# L1Demoscene_v4.net
KiCad netlist of a schematic drawn in EAGLE
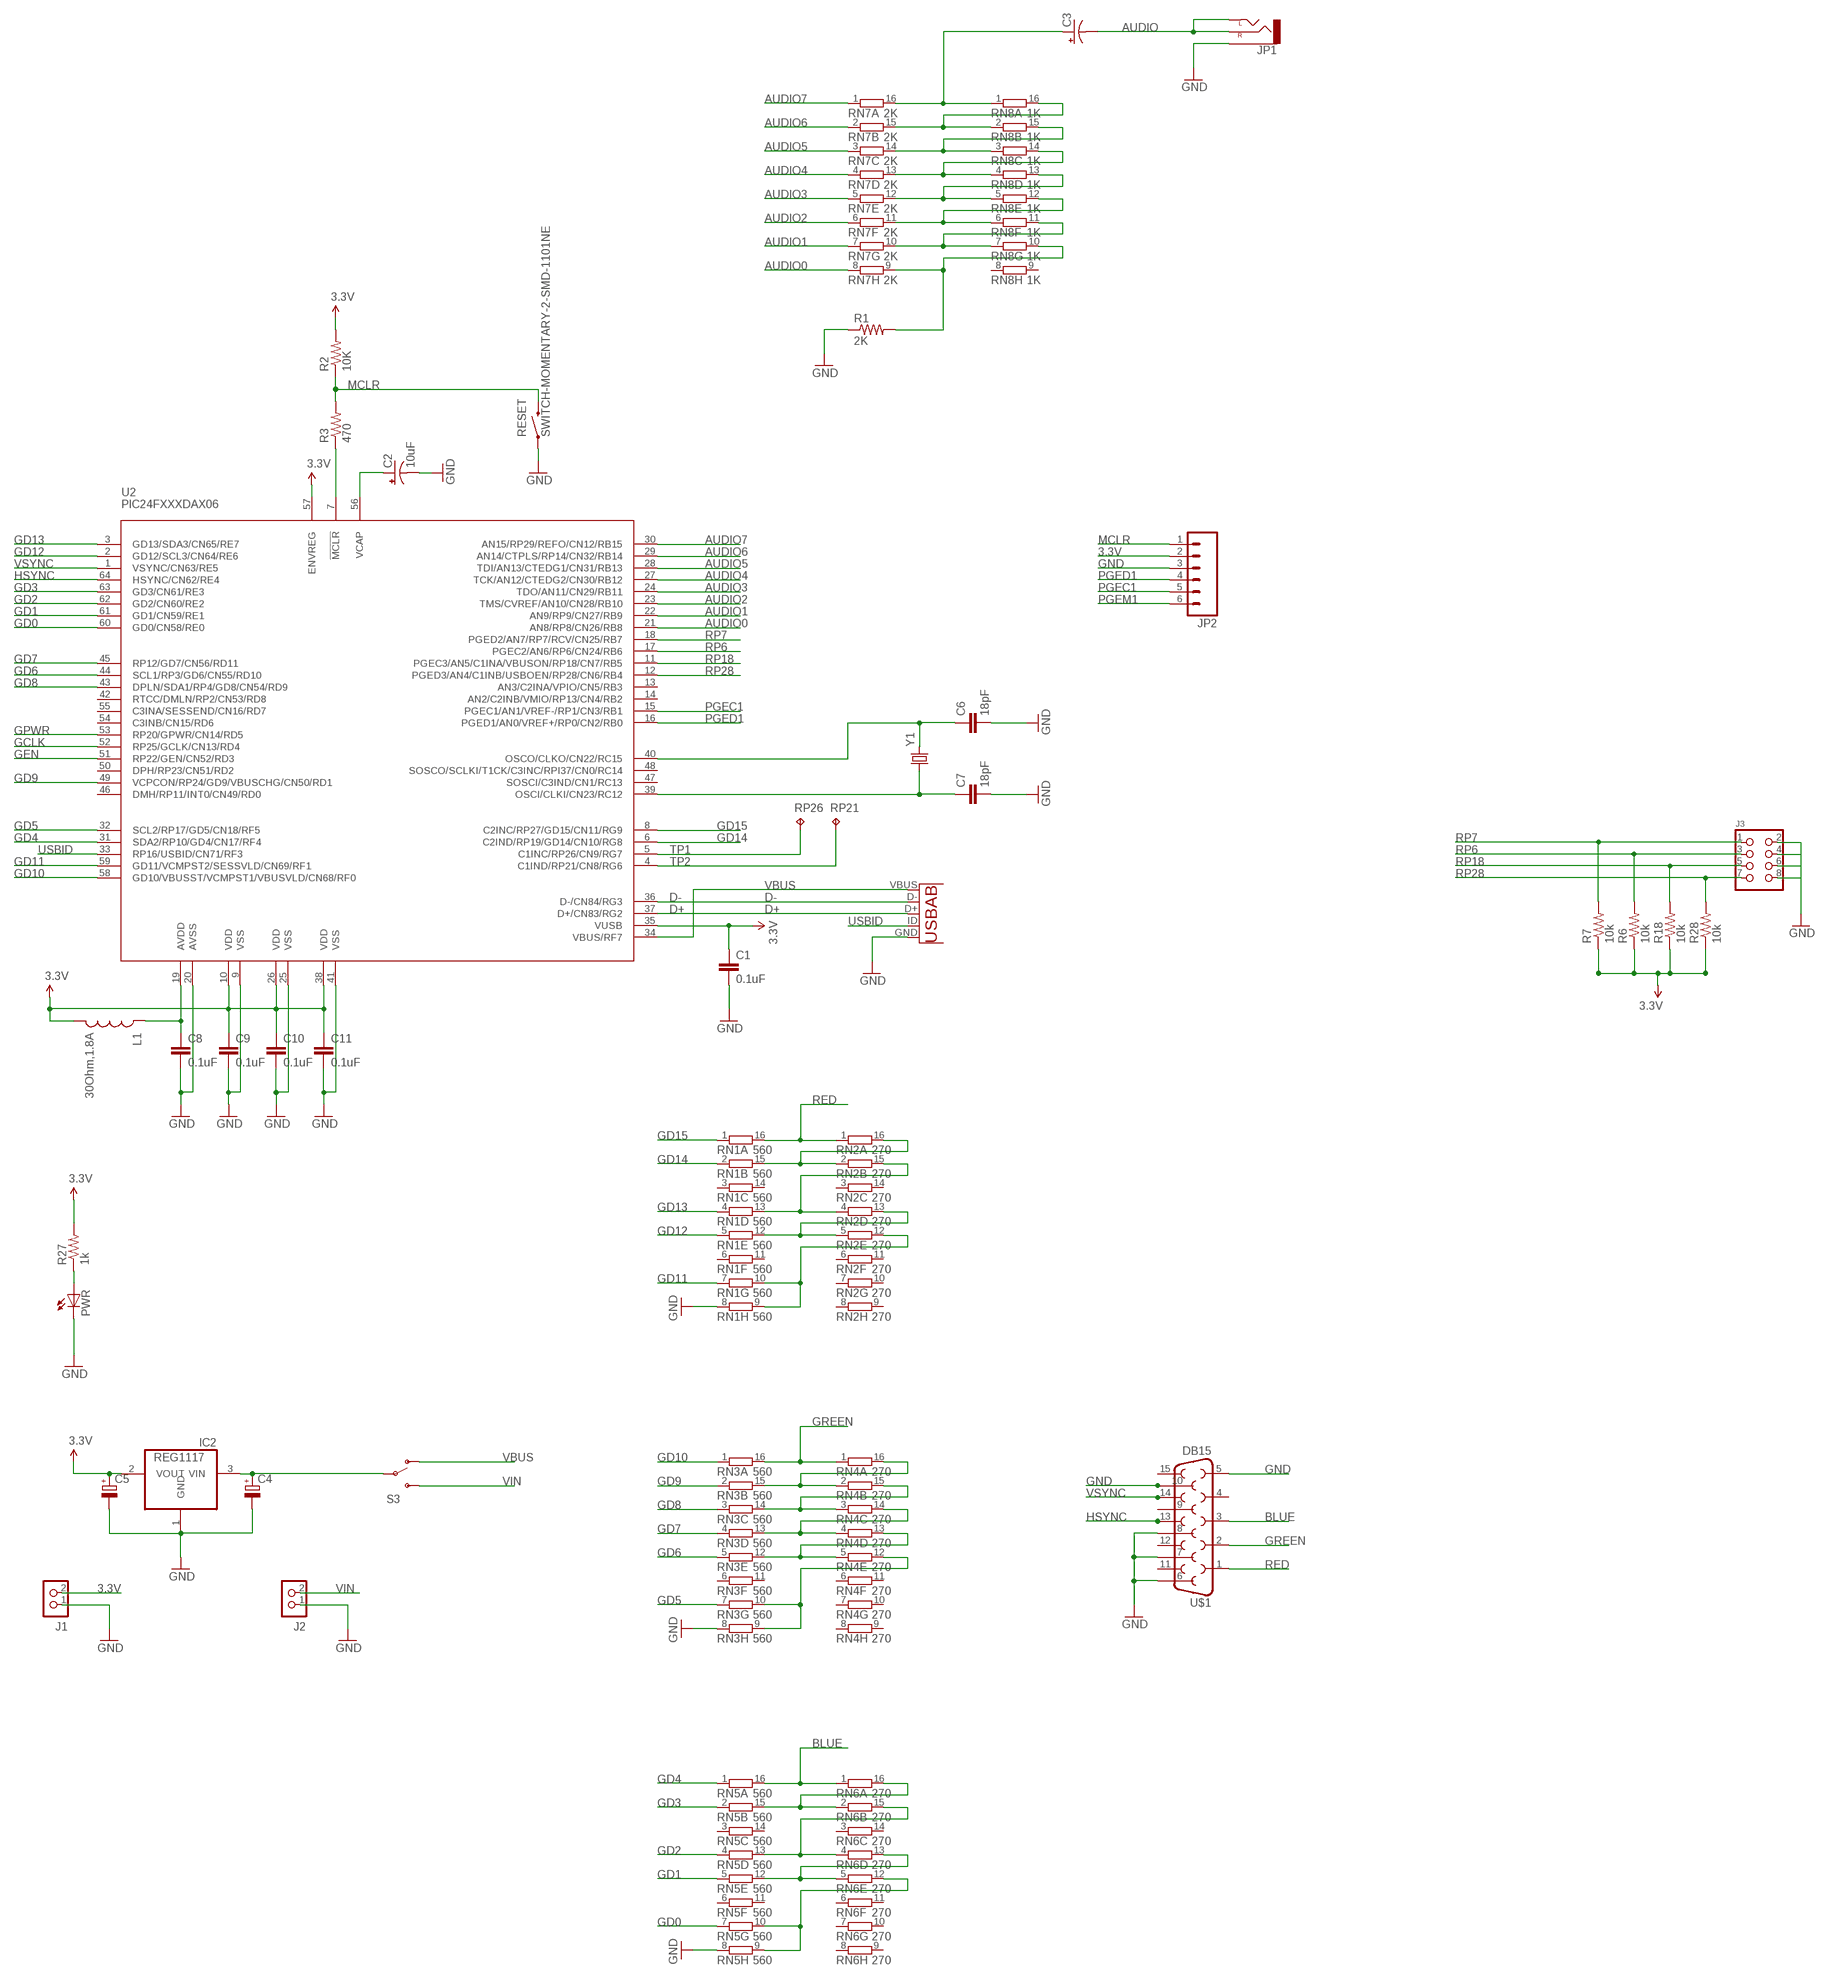
[diagram p0: schematic, sheet 1]

(export (version "E")
  (design (tool "Eeschema 10.0.6"))
  (components
    (comp (ref "C1")
      (value "0.1uF")
      (footprint "eagle-import:0603-CAP")
      (libsource (lib "eagle-import") (part "CAP0603-CAP"))
    )
    (comp (ref "C2")
      (value "10uF")
      (footprint "eagle-import:EIA3216")
      (libsource (lib "eagle-import") (part "CAP_POL1206"))
    )
    (comp (ref "C3")
      (value "CAP_POL1206")
      (footprint "eagle-import:EIA3216")
      (libsource (lib "eagle-import") (part "CAP_POL1206"))
    )
    (comp (ref "C4")
      (value "CAPACITOR_POL-SMC_A")
      (footprint "eagle-import:SMC_A")
      (libsource (lib "eagle-import") (part "CAPACITOR_POL-SMC_A"))
    )
    (comp (ref "C5")
      (value "CAPACITOR_POL-SMC_A")
      (footprint "eagle-import:SMC_A")
      (libsource (lib "eagle-import") (part "CAPACITOR_POL-SMC_A"))
    )
    (comp (ref "C6")
      (value "18pF")
      (footprint "eagle-import:0603-CAP")
      (libsource (lib "eagle-import") (part "CAP0603-CAP"))
    )
    (comp (ref "C7")
      (value "18pF")
      (footprint "eagle-import:0603-CAP")
      (libsource (lib "eagle-import") (part "CAP0603-CAP"))
    )
    (comp (ref "C8")
      (value "0.1uF")
      (footprint "eagle-import:0603-CAP")
      (libsource (lib "eagle-import") (part "CAP0603-CAP"))
    )
    (comp (ref "C9")
      (value "0.1uF")
      (footprint "eagle-import:0603-CAP")
      (libsource (lib "eagle-import") (part "CAP0603-CAP"))
    )
    (comp (ref "C10")
      (value "0.1uF")
      (footprint "eagle-import:0603-CAP")
      (libsource (lib "eagle-import") (part "CAP0603-CAP"))
    )
    (comp (ref "C11")
      (value "0.1uF")
      (footprint "eagle-import:0603-CAP")
      (libsource (lib "eagle-import") (part "CAP0603-CAP"))
    )
    (comp (ref "IC2")
      (value "REG1117")
      (footprint "eagle-import:SOT223")
      (libsource (lib "eagle-import") (part "REG1117"))
    )
    (comp (ref "J1")
      (value "CON_HEADER_1X02-PTH")
      (footprint "eagle-import:M1X2")
      (libsource (lib "eagle-import") (part "CON_HEADER_1X02-PTH"))
    )
    (comp (ref "J2")
      (value "CON_HEADER_1X02-PTH")
      (footprint "eagle-import:M1X2")
      (libsource (lib "eagle-import") (part "CON_HEADER_1X02-PTH"))
    )
    (comp (ref "J3")
      (value "CON_HEADER_2X04-PTH")
      (footprint "eagle-import:M2X4")
      (libsource (lib "eagle-import") (part "CON_HEADER_2X04-PTH"))
    )
    (comp (ref "JP1")
      (value "AUDIO-JACKPTH")
      (footprint "eagle-import:AUDIO-JACK")
      (libsource (lib "eagle-import") (part "AUDIO-JACKPTH"))
    )
    (comp (ref "JP2")
      (value "M06SIP")
      (footprint "eagle-import:1X06")
      (libsource (lib "eagle-import") (part "M06SIP"))
    )
    (comp (ref "L1")
      (value "30Ohm,1.8A")
      (footprint "eagle-import:0603")
      (libsource (lib "eagle-import") (part "INDUCTOR0603"))
    )
    (comp (ref "PWR")
      (value "LED-0603")
      (footprint "eagle-import:LED-603")
      (libsource (lib "eagle-import") (part "LED-0603"))
    )
    (comp (ref "R1")
      (value "2K")
      (footprint "eagle-import:0603-RES")
      (libsource (lib "eagle-import") (part "RESISTOR0603-RES"))
    )
    (comp (ref "R2")
      (value "10K")
      (footprint "eagle-import:0603-RES")
      (libsource (lib "eagle-import") (part "RESISTOR0603-RES"))
    )
    (comp (ref "R3")
      (value "470")
      (footprint "eagle-import:0603-RES")
      (libsource (lib "eagle-import") (part "RESISTOR0603-RES"))
    )
    (comp (ref "R6")
      (value "10k")
      (footprint "eagle-import:0603-RES")
      (libsource (lib "eagle-import") (part "RESISTOR0603-RES"))
    )
    (comp (ref "R7")
      (value "10k")
      (footprint "eagle-import:0603-RES")
      (libsource (lib "eagle-import") (part "RESISTOR0603-RES"))
    )
    (comp (ref "R18")
      (value "10k")
      (footprint "eagle-import:0603-RES")
      (libsource (lib "eagle-import") (part "RESISTOR0603-RES"))
    )
    (comp (ref "R27")
      (value "1k")
      (footprint "eagle-import:0603-RES")
      (libsource (lib "eagle-import") (part "RESISTOR0603-RES"))
    )
    (comp (ref "R28")
      (value "10k")
      (footprint "eagle-import:0603-RES")
      (libsource (lib "eagle-import") (part "RESISTOR0603-RES"))
    )
    (comp (ref "RESET")
      (value "SWITCH-MOMENTARY-2-SMD-1101NE")
      (footprint "eagle-import:TACTILE-SWITCH-1101NE")
      (libsource (lib "eagle-import") (part "SWITCH-MOMENTARY-2-SMD-1101NE"))
    )
    (comp (ref "RN1")
      (value "560")
      (footprint "eagle-import:EXB2HV")
      (libsource (lib "eagle-import") (part "8R-NEXB2HV"))
    )
    (comp (ref "RN2")
      (value "270")
      (footprint "eagle-import:EXB2HV")
      (libsource (lib "eagle-import") (part "8R-NEXB2HV"))
    )
    (comp (ref "RN3")
      (value "560")
      (footprint "eagle-import:EXB2HV")
      (libsource (lib "eagle-import") (part "8R-NEXB2HV"))
    )
    (comp (ref "RN4")
      (value "270")
      (footprint "eagle-import:EXB2HV")
      (libsource (lib "eagle-import") (part "8R-NEXB2HV"))
    )
    (comp (ref "RN5")
      (value "560")
      (footprint "eagle-import:EXB2HV")
      (libsource (lib "eagle-import") (part "8R-NEXB2HV"))
    )
    (comp (ref "RN6")
      (value "270")
      (footprint "eagle-import:EXB2HV")
      (libsource (lib "eagle-import") (part "8R-NEXB2HV"))
    )
    (comp (ref "RN7")
      (value "2K")
      (footprint "eagle-import:EXB2HV")
      (libsource (lib "eagle-import") (part "8R-NEXB2HV"))
    )
    (comp (ref "RN8")
      (value "1K")
      (footprint "eagle-import:EXB2HV")
      (libsource (lib "eagle-import") (part "8R-NEXB2HV"))
    )
    (comp (ref "RP21")
      (value "TPTP06R")
      (footprint "eagle-import:TP06R")
      (libsource (lib "eagle-import") (part "TPTP06R"))
    )
    (comp (ref "RP26")
      (value "TPTP06R")
      (footprint "eagle-import:TP06R")
      (libsource (lib "eagle-import") (part "TPTP06R"))
    )
    (comp (ref "S3")
      (value "SWITCH-SPDT-SMD-A")
      (footprint "eagle-import:SWITCH-SPST-SMD-A")
      (libsource (lib "eagle-import") (part "SWITCH-SPDT-SMD-A"))
    )
    (comp (ref "U$1")
      (value "DB15")
      (footprint "eagle-import:DB15")
      (libsource (lib "eagle-import") (part "DB15"))
    )
    (comp (ref "U2")
      (value "PIC24FXXXDAX06")
      (footprint "eagle-import:PIC24FXXX_TQFP64")
      (libsource (lib "eagle-import") (part "PIC24FXXXDAX06"))
    )
    (comp (ref "U3")
      (value "USB-AB")
      (footprint "eagle-import:USB-AB-MICRO-SMD")
      (libsource (lib "eagle-import") (part "USB-AB"))
    )
    (comp (ref "Y1")
      (value "CRYSTAL5X3")
      (footprint "eagle-import:CRYSTAL-SMD-5X3")
      (libsource (lib "eagle-import") (part "CRYSTAL5X3"))
    )
  )
  (nets
    (net (code "1") (name "/AUDIO") (class "Default")
      (node (ref "C3") (pin "C") (pinfunction "-_C") (pintype "passive"))
      (node (ref "JP1") (pin "RING") (pinfunction "RIGHT_RING") (pintype "bidirectional"))
      (node (ref "JP1") (pin "TIP") (pinfunction "LEFT_TIP") (pintype "bidirectional"))
    )
    (net (code "2") (name "/AUDIO0") (class "Default")
      (node (ref "RN7") (pin "8") (pinfunction "1_8") (pintype "passive"))
      (node (ref "U2") (pin "21") (pinfunction "AN8/RP8/CN26/RB8_21") (pintype "bidirectional"))
    )
    (net (code "3") (name "/AUDIO1") (class "Default")
      (node (ref "RN7") (pin "7") (pinfunction "1_7") (pintype "passive"))
      (node (ref "U2") (pin "22") (pinfunction "AN9/RP9/CN27/RB9_22") (pintype "bidirectional"))
    )
    (net (code "4") (name "/AUDIO2") (class "Default")
      (node (ref "RN7") (pin "6") (pinfunction "1_6") (pintype "passive"))
      (node (ref "U2") (pin "23") (pinfunction "TMS/CVREF/AN10/CN28/RB10_23") (pintype "bidirectional"))
    )
    (net (code "5") (name "/AUDIO3") (class "Default")
      (node (ref "RN7") (pin "5") (pinfunction "1_5") (pintype "passive"))
      (node (ref "U2") (pin "24") (pinfunction "TDO/AN11/CN29/RB11_24") (pintype "bidirectional"))
    )
    (net (code "6") (name "/AUDIO4") (class "Default")
      (node (ref "RN7") (pin "4") (pinfunction "1_4") (pintype "passive"))
      (node (ref "U2") (pin "27") (pinfunction "TCK/AN12/CTEDG2/CN30/RB12_27") (pintype "bidirectional"))
    )
    (net (code "7") (name "/AUDIO5") (class "Default")
      (node (ref "RN7") (pin "3") (pinfunction "1_3") (pintype "passive"))
      (node (ref "U2") (pin "28") (pinfunction "TDI/AN13/CTEDG1/CN31/RB13_28") (pintype "bidirectional"))
    )
    (net (code "8") (name "/AUDIO6") (class "Default")
      (node (ref "RN7") (pin "2") (pinfunction "1_2") (pintype "passive"))
      (node (ref "U2") (pin "29") (pinfunction "AN14/CTPLS/RP14/CN32/RB14_29") (pintype "bidirectional"))
    )
    (net (code "9") (name "/AUDIO7") (class "Default")
      (node (ref "RN7") (pin "1") (pinfunction "1_1") (pintype "passive"))
      (node (ref "U2") (pin "30") (pinfunction "AN15/RP29/REFO/CN12/RB15_30") (pintype "bidirectional"))
    )
    (net (code "10") (name "/BLUE") (class "Default")
      (node (ref "RN5") (pin "16") (pinfunction "2_16") (pintype "passive"))
      (node (ref "RN6") (pin "1") (pinfunction "1_1") (pintype "passive"))
      (node (ref "U$1") (pin "3") (pinfunction "3_3") (pintype "passive"))
    )
    (net (code "11") (name "/D+") (class "Default")
      (node (ref "U2") (pin "37") (pinfunction "D+/CN83/RG2_37") (pintype "bidirectional"))
      (node (ref "U3") (pin "D+") (pinfunction "D+_D+") (pintype "bidirectional"))
    )
    (net (code "12") (name "/D-") (class "Default")
      (node (ref "U2") (pin "36") (pinfunction "D-/CN84/RG3_36") (pintype "bidirectional"))
      (node (ref "U3") (pin "D-") (pinfunction "D-_D-") (pintype "bidirectional"))
    )
    (net (code "13") (name "/GCLK") (class "Default")
      (node (ref "U2") (pin "52") (pinfunction "RP25/GCLK/CN13/RD4_52") (pintype "bidirectional"))
    )
    (net (code "14") (name "/GD0") (class "Default")
      (node (ref "RN5") (pin "7") (pinfunction "1_7") (pintype "passive"))
      (node (ref "U2") (pin "60") (pinfunction "GD0/CN58/RE0_60") (pintype "bidirectional"))
    )
    (net (code "15") (name "/GD1") (class "Default")
      (node (ref "RN5") (pin "5") (pinfunction "1_5") (pintype "passive"))
      (node (ref "U2") (pin "61") (pinfunction "GD1/CN59/RE1_61") (pintype "bidirectional"))
    )
    (net (code "16") (name "/GD2") (class "Default")
      (node (ref "RN5") (pin "4") (pinfunction "1_4") (pintype "passive"))
      (node (ref "U2") (pin "62") (pinfunction "GD2/CN60/RE2_62") (pintype "bidirectional"))
    )
    (net (code "17") (name "/GD3") (class "Default")
      (node (ref "RN5") (pin "2") (pinfunction "1_2") (pintype "passive"))
      (node (ref "U2") (pin "63") (pinfunction "GD3/CN61/RE3_63") (pintype "bidirectional"))
    )
    (net (code "18") (name "/GD4") (class "Default")
      (node (ref "RN5") (pin "1") (pinfunction "1_1") (pintype "passive"))
      (node (ref "U2") (pin "31") (pinfunction "SDA2/RP10/GD4/CN17/RF4_31") (pintype "bidirectional"))
    )
    (net (code "19") (name "/GD5") (class "Default")
      (node (ref "RN3") (pin "7") (pinfunction "1_7") (pintype "passive"))
      (node (ref "U2") (pin "32") (pinfunction "SCL2/RP17/GD5/CN18/RF5_32") (pintype "bidirectional"))
    )
    (net (code "20") (name "/GD6") (class "Default")
      (node (ref "RN3") (pin "5") (pinfunction "1_5") (pintype "passive"))
      (node (ref "U2") (pin "44") (pinfunction "SCL1/RP3/GD6/CN55/RD10_44") (pintype "bidirectional"))
    )
    (net (code "21") (name "/GD7") (class "Default")
      (node (ref "RN3") (pin "4") (pinfunction "1_4") (pintype "passive"))
      (node (ref "U2") (pin "45") (pinfunction "RP12/GD7/CN56/RD11_45") (pintype "bidirectional"))
    )
    (net (code "22") (name "/GD8") (class "Default")
      (node (ref "RN3") (pin "3") (pinfunction "1_3") (pintype "passive"))
      (node (ref "U2") (pin "43") (pinfunction "DPLN/SDA1/RP4/GD8/CN54/RD9_43") (pintype "bidirectional"))
    )
    (net (code "23") (name "/GD9") (class "Default")
      (node (ref "RN3") (pin "2") (pinfunction "1_2") (pintype "passive"))
      (node (ref "U2") (pin "49") (pinfunction "VCPCON/RP24/GD9/VBUSCHG/CN50/RD1_49") (pintype "bidirectional"))
    )
    (net (code "24") (name "/GD10") (class "Default")
      (node (ref "RN3") (pin "1") (pinfunction "1_1") (pintype "passive"))
      (node (ref "U2") (pin "58") (pinfunction "GD10/VBUSST/VCMPST1/VBUSVLD/CN68/RF0_58") (pintype "bidirectional"))
    )
    (net (code "25") (name "/GD11") (class "Default")
      (node (ref "RN1") (pin "7") (pinfunction "1_7") (pintype "passive"))
      (node (ref "U2") (pin "59") (pinfunction "GD11/VCMPST2/SESSVLD/CN69/RF1_59") (pintype "bidirectional"))
    )
    (net (code "26") (name "/GD12") (class "Default")
      (node (ref "RN1") (pin "5") (pinfunction "1_5") (pintype "passive"))
      (node (ref "U2") (pin "2") (pinfunction "GD12/SCL3/CN64/RE6_2") (pintype "bidirectional"))
    )
    (net (code "27") (name "/GD13") (class "Default")
      (node (ref "RN1") (pin "4") (pinfunction "1_4") (pintype "passive"))
      (node (ref "U2") (pin "3") (pinfunction "GD13/SDA3/CN65/RE7_3") (pintype "bidirectional"))
    )
    (net (code "28") (name "/GD14") (class "Default")
      (node (ref "RN1") (pin "2") (pinfunction "1_2") (pintype "passive"))
      (node (ref "U2") (pin "6") (pinfunction "C2IND/RP19/GD14/CN10/RG8_6") (pintype "bidirectional"))
    )
    (net (code "29") (name "/GD15") (class "Default")
      (node (ref "RN1") (pin "1") (pinfunction "1_1") (pintype "passive"))
      (node (ref "U2") (pin "8") (pinfunction "C2INC/RP27/GD15/CN11/RG9_8") (pintype "bidirectional"))
    )
    (net (code "30") (name "/GEN") (class "Default")
      (node (ref "U2") (pin "51") (pinfunction "RP22/GEN/CN52/RD3_51") (pintype "bidirectional"))
    )
    (net (code "31") (name "/GPWR") (class "Default")
      (node (ref "U2") (pin "53") (pinfunction "RP20/GPWR/CN14/RD5_53") (pintype "bidirectional"))
    )
    (net (code "32") (name "/GREEN") (class "Default")
      (node (ref "RN3") (pin "16") (pinfunction "2_16") (pintype "passive"))
      (node (ref "RN4") (pin "1") (pinfunction "1_1") (pintype "passive"))
      (node (ref "U$1") (pin "2") (pinfunction "2_2") (pintype "passive"))
    )
    (net (code "33") (name "/HSYNC") (class "Default")
      (node (ref "U$1") (pin "13") (pinfunction "13_13") (pintype "passive"))
      (node (ref "U2") (pin "64") (pinfunction "HSYNC/CN62/RE4_64") (pintype "bidirectional"))
    )
    (net (code "34") (name "/MCLR") (class "Default")
      (node (ref "JP2") (pin "1") (pinfunction "1_1") (pintype "passive"))
      (node (ref "R2") (pin "1") (pinfunction "1_1") (pintype "passive"))
      (node (ref "R3") (pin "2") (pinfunction "2_2") (pintype "passive"))
      (node (ref "RESET") (pin "P$2") (pinfunction "2_P$2") (pintype "passive"))
    )
    (net (code "35") (name "/PGEC1") (class "Default")
      (node (ref "JP2") (pin "5") (pinfunction "5_5") (pintype "passive"))
      (node (ref "U2") (pin "15") (pinfunction "PGEC1/AN1/VREF-/RP1/CN3/RB1_15") (pintype "bidirectional"))
    )
    (net (code "36") (name "/PGED1") (class "Default")
      (node (ref "JP2") (pin "4") (pinfunction "4_4") (pintype "passive"))
      (node (ref "U2") (pin "16") (pinfunction "PGED1/AN0/VREF+/RP0/CN2/RB0_16") (pintype "bidirectional"))
    )
    (net (code "37") (name "/PGEM1") (class "Default")
      (node (ref "JP2") (pin "6") (pinfunction "6_6") (pintype "passive"))
    )
    (net (code "38") (name "/RED") (class "Default")
      (node (ref "RN1") (pin "16") (pinfunction "2_16") (pintype "passive"))
      (node (ref "RN2") (pin "1") (pinfunction "1_1") (pintype "passive"))
      (node (ref "U$1") (pin "1") (pinfunction "1_1") (pintype "passive"))
    )
    (net (code "39") (name "/RP6") (class "Default")
      (node (ref "J3") (pin "3") (pinfunction "P$3_3") (pintype "passive"))
      (node (ref "R6") (pin "2") (pinfunction "2_2") (pintype "passive"))
      (node (ref "U2") (pin "17") (pinfunction "PGEC2/AN6/RP6/CN24/RB6_17") (pintype "bidirectional"))
    )
    (net (code "40") (name "/RP7") (class "Default")
      (node (ref "J3") (pin "1") (pinfunction "P$1_1") (pintype "passive"))
      (node (ref "R7") (pin "2") (pinfunction "2_2") (pintype "passive"))
      (node (ref "U2") (pin "18") (pinfunction "PGED2/AN7/RP7/RCV/CN25/RB7_18") (pintype "bidirectional"))
    )
    (net (code "41") (name "/RP18") (class "Default")
      (node (ref "J3") (pin "5") (pinfunction "P$5_5") (pintype "passive"))
      (node (ref "R18") (pin "2") (pinfunction "2_2") (pintype "passive"))
      (node (ref "U2") (pin "11") (pinfunction "PGEC3/AN5/C1INA/VBUSON/RP18/CN7/RB5_11") (pintype "bidirectional"))
    )
    (net (code "42") (name "/RP28") (class "Default")
      (node (ref "J3") (pin "7") (pinfunction "P$7_7") (pintype "passive"))
      (node (ref "R28") (pin "2") (pinfunction "2_2") (pintype "passive"))
      (node (ref "U2") (pin "12") (pinfunction "PGED3/AN4/C1INB/USBOEN/RP28/CN6/RB4_12") (pintype "bidirectional"))
    )
    (net (code "43") (name "/TP1") (class "Default")
      (node (ref "RP26") (pin "TP") (pinfunction "TP_TP") (pintype "input"))
      (node (ref "U2") (pin "5") (pinfunction "C1INC/RP26/CN9/RG7_5") (pintype "bidirectional"))
    )
    (net (code "44") (name "/TP2") (class "Default")
      (node (ref "RP21") (pin "TP") (pinfunction "TP_TP") (pintype "input"))
      (node (ref "U2") (pin "4") (pinfunction "C1IND/RP21/CN8/RG6_4") (pintype "bidirectional"))
    )
    (net (code "45") (name "/USBID") (class "Default")
      (node (ref "U2") (pin "33") (pinfunction "RP16/USBID/CN71/RF3_33") (pintype "bidirectional"))
      (node (ref "U3") (pin "ID") (pinfunction "USBID_ID") (pintype "bidirectional"))
    )
    (net (code "46") (name "/VBUS") (class "Default")
      (node (ref "S3") (pin "1") (pinfunction "O_1") (pintype "passive"))
      (node (ref "U2") (pin "34") (pinfunction "VBUS/RF7_34") (pintype "input"))
      (node (ref "U3") (pin "VBUS") (pinfunction "VBUS_VBUS") (pintype "bidirectional"))
    )
    (net (code "47") (name "/VIN") (class "Default")
      (node (ref "J2") (pin "2") (pinfunction "2_2") (pintype "passive"))
      (node (ref "S3") (pin "3") (pinfunction "S_3") (pintype "passive"))
    )
    (net (code "48") (name "/VSYNC") (class "Default")
      (node (ref "U$1") (pin "14") (pinfunction "14_14") (pintype "passive"))
      (node (ref "U2") (pin "1") (pinfunction "VSYNC/CN63/RE5_1") (pintype "bidirectional"))
    )
    (net (code "49") (name "3.3V") (class "Default")
      (node (ref "C1") (pin "1") (pinfunction "1_1") (pintype "passive"))
      (node (ref "C10") (pin "1") (pinfunction "1_1") (pintype "passive"))
      (node (ref "C11") (pin "1") (pinfunction "1_1") (pintype "passive"))
      (node (ref "C5") (pin "+") (pinfunction "+_+") (pintype "passive"))
      (node (ref "C9") (pin "1") (pinfunction "1_1") (pintype "passive"))
      (node (ref "IC2") (pin "2") (pinfunction "VOUT_2") (pintype "output"))
      (node (ref "J1") (pin "2") (pinfunction "2_2") (pintype "passive"))
      (node (ref "JP2") (pin "2") (pinfunction "2_2") (pintype "passive"))
      (node (ref "L1") (pin "2") (pinfunction "2_2") (pintype "passive"))
      (node (ref "R18") (pin "1") (pinfunction "1_1") (pintype "passive"))
      (node (ref "R2") (pin "2") (pinfunction "2_2") (pintype "passive"))
      (node (ref "R27") (pin "2") (pinfunction "2_2") (pintype "passive"))
      (node (ref "R28") (pin "1") (pinfunction "1_1") (pintype "passive"))
      (node (ref "R6") (pin "1") (pinfunction "1_1") (pintype "passive"))
      (node (ref "R7") (pin "1") (pinfunction "1_1") (pintype "passive"))
      (node (ref "U2") (pin "10") (pinfunction "VDD_10") (pintype "power_in"))
      (node (ref "U2") (pin "26") (pinfunction "VDD_26") (pintype "power_in"))
      (node (ref "U2") (pin "35") (pinfunction "VUSB_35") (pintype "power_in"))
      (node (ref "U2") (pin "38") (pinfunction "VDD_38") (pintype "power_in"))
      (node (ref "U2") (pin "57") (pinfunction "ENVREG_57") (pintype "input"))
    )
    (net (code "50") (name "GND") (class "Default")
      (node (ref "C1") (pin "2") (pinfunction "2_2") (pintype "passive"))
      (node (ref "C10") (pin "2") (pinfunction "2_2") (pintype "passive"))
      (node (ref "C11") (pin "2") (pinfunction "2_2") (pintype "passive"))
      (node (ref "C2") (pin "C") (pinfunction "-_C") (pintype "passive"))
      (node (ref "C4") (pin "-") (pinfunction "-_-") (pintype "passive"))
      (node (ref "C5") (pin "-") (pinfunction "-_-") (pintype "passive"))
      (node (ref "C6") (pin "2") (pinfunction "2_2") (pintype "passive"))
      (node (ref "C7") (pin "2") (pinfunction "2_2") (pintype "passive"))
      (node (ref "C8") (pin "2") (pinfunction "2_2") (pintype "passive"))
      (node (ref "C9") (pin "2") (pinfunction "2_2") (pintype "passive"))
      (node (ref "IC2") (pin "1") (pinfunction "GND_1") (pintype "power_in"))
      (node (ref "J1") (pin "1") (pinfunction "1_1") (pintype "passive"))
      (node (ref "J2") (pin "1") (pinfunction "1_1") (pintype "passive"))
      (node (ref "J3") (pin "2") (pinfunction "P$2_2") (pintype "passive"))
      (node (ref "J3") (pin "4") (pinfunction "P$4_4") (pintype "passive"))
      (node (ref "J3") (pin "6") (pinfunction "P$6_6") (pintype "passive"))
      (node (ref "J3") (pin "8") (pinfunction "P$8_8") (pintype "passive"))
      (node (ref "JP1") (pin "SLEEVE") (pinfunction "SLEEVE_SLEEVE") (pintype "bidirectional"))
      (node (ref "JP2") (pin "3") (pinfunction "3_3") (pintype "passive"))
      (node (ref "PWR") (pin "C") (pinfunction "C_C") (pintype "passive"))
      (node (ref "R1") (pin "1") (pinfunction "1_1") (pintype "passive"))
      (node (ref "RESET") (pin "P$1") (pinfunction "1_P$1") (pintype "passive"))
      (node (ref "RN1") (pin "8") (pinfunction "1_8") (pintype "passive"))
      (node (ref "RN3") (pin "8") (pinfunction "1_8") (pintype "passive"))
      (node (ref "RN5") (pin "8") (pinfunction "1_8") (pintype "passive"))
      (node (ref "U$1") (pin "10") (pinfunction "10_10") (pintype "passive"))
      (node (ref "U$1") (pin "5") (pinfunction "5_5") (pintype "passive"))
      (node (ref "U$1") (pin "6") (pinfunction "6_6") (pintype "passive"))
      (node (ref "U$1") (pin "7") (pinfunction "7_7") (pintype "passive"))
      (node (ref "U$1") (pin "8") (pinfunction "8_8") (pintype "passive"))
      (node (ref "U2") (pin "20") (pinfunction "AVSS_20") (pintype "power_in"))
      (node (ref "U2") (pin "25") (pinfunction "VSS_25") (pintype "power_in"))
      (node (ref "U2") (pin "41") (pinfunction "VSS_41") (pintype "power_in"))
      (node (ref "U2") (pin "9") (pinfunction "VSS_9") (pintype "power_in"))
      (node (ref "U3") (pin "GND") (pinfunction "GND_GND") (pintype "bidirectional"))
    )
    (net (code "51") (name "Net-(C2-+)") (class "Default")
      (node (ref "C2") (pin "A") (pinfunction "+_A") (pintype "passive"))
      (node (ref "U2") (pin "56") (pinfunction "VCAP_56") (pintype "power_in"))
    )
    (net (code "52") (name "Net-(C3-+)") (class "Default")
      (node (ref "C3") (pin "A") (pinfunction "+_A") (pintype "passive"))
      (node (ref "RN7") (pin "16") (pinfunction "2_16") (pintype "passive"))
      (node (ref "RN8") (pin "1") (pinfunction "1_1") (pintype "passive"))
    )
    (net (code "53") (name "Net-(IC2-VIN)") (class "Default")
      (node (ref "C4") (pin "+") (pinfunction "+_+") (pintype "passive"))
      (node (ref "IC2") (pin "3") (pinfunction "VIN_3") (pintype "input"))
      (node (ref "S3") (pin "2") (pinfunction "P_2") (pintype "passive"))
    )
    (net (code "54") (name "Net-(PWR-PadA)") (class "Default")
      (node (ref "PWR") (pin "A") (pinfunction "A_A") (pintype "passive"))
      (node (ref "R27") (pin "1") (pinfunction "1_1") (pintype "passive"))
    )
    (net (code "55") (name "Net-(RN1B-2)") (class "Default")
      (node (ref "RN1") (pin "15") (pinfunction "2_15") (pintype "passive"))
      (node (ref "RN2") (pin "16") (pinfunction "2_16") (pintype "passive"))
      (node (ref "RN2") (pin "2") (pinfunction "1_2") (pintype "passive"))
    )
    (net (code "56") (name "Net-(RN1D-2)") (class "Default")
      (node (ref "RN1") (pin "13") (pinfunction "2_13") (pintype "passive"))
      (node (ref "RN2") (pin "15") (pinfunction "2_15") (pintype "passive"))
      (node (ref "RN2") (pin "4") (pinfunction "1_4") (pintype "passive"))
    )
    (net (code "57") (name "Net-(RN1E-2)") (class "Default")
      (node (ref "RN1") (pin "12") (pinfunction "2_12") (pintype "passive"))
      (node (ref "RN2") (pin "13") (pinfunction "2_13") (pintype "passive"))
      (node (ref "RN2") (pin "5") (pinfunction "1_5") (pintype "passive"))
    )
    (net (code "58") (name "Net-(RN1G-2)") (class "Default")
      (node (ref "RN1") (pin "10") (pinfunction "2_10") (pintype "passive"))
      (node (ref "RN1") (pin "9") (pinfunction "2_9") (pintype "passive"))
      (node (ref "RN2") (pin "12") (pinfunction "2_12") (pintype "passive"))
    )
    (net (code "59") (name "Net-(RN3B-2)") (class "Default")
      (node (ref "RN3") (pin "15") (pinfunction "2_15") (pintype "passive"))
      (node (ref "RN4") (pin "16") (pinfunction "2_16") (pintype "passive"))
      (node (ref "RN4") (pin "2") (pinfunction "1_2") (pintype "passive"))
    )
    (net (code "60") (name "Net-(RN3C-2)") (class "Default")
      (node (ref "RN3") (pin "14") (pinfunction "2_14") (pintype "passive"))
      (node (ref "RN4") (pin "15") (pinfunction "2_15") (pintype "passive"))
      (node (ref "RN4") (pin "3") (pinfunction "1_3") (pintype "passive"))
    )
    (net (code "61") (name "Net-(RN3D-2)") (class "Default")
      (node (ref "RN3") (pin "13") (pinfunction "2_13") (pintype "passive"))
      (node (ref "RN4") (pin "14") (pinfunction "2_14") (pintype "passive"))
      (node (ref "RN4") (pin "4") (pinfunction "1_4") (pintype "passive"))
    )
    (net (code "62") (name "Net-(RN3E-2)") (class "Default")
      (node (ref "RN3") (pin "12") (pinfunction "2_12") (pintype "passive"))
      (node (ref "RN4") (pin "13") (pinfunction "2_13") (pintype "passive"))
      (node (ref "RN4") (pin "5") (pinfunction "1_5") (pintype "passive"))
    )
    (net (code "63") (name "Net-(RN3G-2)") (class "Default")
      (node (ref "RN3") (pin "10") (pinfunction "2_10") (pintype "passive"))
      (node (ref "RN3") (pin "9") (pinfunction "2_9") (pintype "passive"))
      (node (ref "RN4") (pin "12") (pinfunction "2_12") (pintype "passive"))
    )
    (net (code "64") (name "Net-(RN5B-2)") (class "Default")
      (node (ref "RN5") (pin "15") (pinfunction "2_15") (pintype "passive"))
      (node (ref "RN6") (pin "16") (pinfunction "2_16") (pintype "passive"))
      (node (ref "RN6") (pin "2") (pinfunction "1_2") (pintype "passive"))
    )
    (net (code "65") (name "Net-(RN5D-2)") (class "Default")
      (node (ref "RN5") (pin "13") (pinfunction "2_13") (pintype "passive"))
      (node (ref "RN6") (pin "15") (pinfunction "2_15") (pintype "passive"))
      (node (ref "RN6") (pin "4") (pinfunction "1_4") (pintype "passive"))
    )
    (net (code "66") (name "Net-(RN5E-2)") (class "Default")
      (node (ref "RN5") (pin "12") (pinfunction "2_12") (pintype "passive"))
      (node (ref "RN6") (pin "13") (pinfunction "2_13") (pintype "passive"))
      (node (ref "RN6") (pin "5") (pinfunction "1_5") (pintype "passive"))
    )
    (net (code "67") (name "Net-(RN5G-2)") (class "Default")
      (node (ref "RN5") (pin "10") (pinfunction "2_10") (pintype "passive"))
      (node (ref "RN5") (pin "9") (pinfunction "2_9") (pintype "passive"))
      (node (ref "RN6") (pin "12") (pinfunction "2_12") (pintype "passive"))
    )
    (net (code "68") (name "Net-(RN7B-2)") (class "Default")
      (node (ref "RN7") (pin "15") (pinfunction "2_15") (pintype "passive"))
      (node (ref "RN8") (pin "16") (pinfunction "2_16") (pintype "passive"))
      (node (ref "RN8") (pin "2") (pinfunction "1_2") (pintype "passive"))
    )
    (net (code "69") (name "Net-(RN7C-2)") (class "Default")
      (node (ref "RN7") (pin "14") (pinfunction "2_14") (pintype "passive"))
      (node (ref "RN8") (pin "15") (pinfunction "2_15") (pintype "passive"))
      (node (ref "RN8") (pin "3") (pinfunction "1_3") (pintype "passive"))
    )
    (net (code "70") (name "Net-(RN7D-2)") (class "Default")
      (node (ref "RN7") (pin "13") (pinfunction "2_13") (pintype "passive"))
      (node (ref "RN8") (pin "14") (pinfunction "2_14") (pintype "passive"))
      (node (ref "RN8") (pin "4") (pinfunction "1_4") (pintype "passive"))
    )
    (net (code "71") (name "Net-(RN7E-2)") (class "Default")
      (node (ref "RN7") (pin "12") (pinfunction "2_12") (pintype "passive"))
      (node (ref "RN8") (pin "13") (pinfunction "2_13") (pintype "passive"))
      (node (ref "RN8") (pin "5") (pinfunction "1_5") (pintype "passive"))
    )
    (net (code "72") (name "Net-(RN7F-2)") (class "Default")
      (node (ref "RN7") (pin "11") (pinfunction "2_11") (pintype "passive"))
      (node (ref "RN8") (pin "12") (pinfunction "2_12") (pintype "passive"))
      (node (ref "RN8") (pin "6") (pinfunction "1_6") (pintype "passive"))
    )
    (net (code "73") (name "Net-(RN7G-2)") (class "Default")
      (node (ref "RN7") (pin "10") (pinfunction "2_10") (pintype "passive"))
      (node (ref "RN8") (pin "11") (pinfunction "2_11") (pintype "passive"))
      (node (ref "RN8") (pin "7") (pinfunction "1_7") (pintype "passive"))
    )
    (net (code "74") (name "Net-(RN7H-2)") (class "Default")
      (node (ref "R1") (pin "2") (pinfunction "2_2") (pintype "passive"))
      (node (ref "RN7") (pin "9") (pinfunction "2_9") (pintype "passive"))
      (node (ref "RN8") (pin "10") (pinfunction "2_10") (pintype "passive"))
    )
    (net (code "75") (name "Net-(U2-AVDD)") (class "Default")
      (node (ref "C8") (pin "1") (pinfunction "1_1") (pintype "passive"))
      (node (ref "L1") (pin "1") (pinfunction "1_1") (pintype "passive"))
      (node (ref "U2") (pin "19") (pinfunction "AVDD_19") (pintype "power_in"))
    )
    (net (code "76") (name "Net-(U2-OSCI{slash}CLKI{slash}CN23{slash}RC12)") (class "Default")
      (node (ref "C7") (pin "1") (pinfunction "1_1") (pintype "passive"))
      (node (ref "U2") (pin "39") (pinfunction "OSCI/CLKI/CN23/RC12_39") (pintype "bidirectional"))
      (node (ref "Y1") (pin "1") (pinfunction "1_1") (pintype "passive"))
    )
    (net (code "77") (name "Net-(U2-OSCO{slash}CLKO{slash}CN22{slash}RC15)") (class "Default")
      (node (ref "C6") (pin "1") (pinfunction "1_1") (pintype "passive"))
      (node (ref "U2") (pin "40") (pinfunction "OSCO/CLKO/CN22/RC15_40") (pintype "bidirectional"))
      (node (ref "Y1") (pin "3") (pinfunction "2_3") (pintype "passive"))
    )
    (net (code "78") (name "Net-(U2-~{MCLR})") (class "Default")
      (node (ref "R3") (pin "1") (pinfunction "1_1") (pintype "passive"))
      (node (ref "U2") (pin "7") (pinfunction "~{MCLR}_7") (pintype "input"))
    )
    (net (code "79") (name "unconnected-(RN1C-1-Pad3)") (class "Default")
      (node (ref "RN1") (pin "3") (pinfunction "1_3") (pintype "passive"))
    )
    (net (code "80") (name "unconnected-(RN1C-2-Pad14)") (class "Default")
      (node (ref "RN1") (pin "14") (pinfunction "2_14") (pintype "passive"))
    )
    (net (code "81") (name "unconnected-(RN1F-1-Pad6)") (class "Default")
      (node (ref "RN1") (pin "6") (pinfunction "1_6") (pintype "passive"))
    )
    (net (code "82") (name "unconnected-(RN1F-2-Pad11)") (class "Default")
      (node (ref "RN1") (pin "11") (pinfunction "2_11") (pintype "passive"))
    )
    (net (code "83") (name "unconnected-(RN2C-1-Pad3)") (class "Default")
      (node (ref "RN2") (pin "3") (pinfunction "1_3") (pintype "passive"))
    )
    (net (code "84") (name "unconnected-(RN2C-2-Pad14)") (class "Default")
      (node (ref "RN2") (pin "14") (pinfunction "2_14") (pintype "passive"))
    )
    (net (code "85") (name "unconnected-(RN2F-1-Pad6)") (class "Default")
      (node (ref "RN2") (pin "6") (pinfunction "1_6") (pintype "passive"))
    )
    (net (code "86") (name "unconnected-(RN2F-2-Pad11)") (class "Default")
      (node (ref "RN2") (pin "11") (pinfunction "2_11") (pintype "passive"))
    )
    (net (code "87") (name "unconnected-(RN2G-1-Pad7)") (class "Default")
      (node (ref "RN2") (pin "7") (pinfunction "1_7") (pintype "passive"))
    )
    (net (code "88") (name "unconnected-(RN2G-2-Pad10)") (class "Default")
      (node (ref "RN2") (pin "10") (pinfunction "2_10") (pintype "passive"))
    )
    (net (code "89") (name "unconnected-(RN2H-1-Pad8)") (class "Default")
      (node (ref "RN2") (pin "8") (pinfunction "1_8") (pintype "passive"))
    )
    (net (code "90") (name "unconnected-(RN2H-2-Pad9)") (class "Default")
      (node (ref "RN2") (pin "9") (pinfunction "2_9") (pintype "passive"))
    )
    (net (code "91") (name "unconnected-(RN3F-1-Pad6)") (class "Default")
      (node (ref "RN3") (pin "6") (pinfunction "1_6") (pintype "passive"))
    )
    (net (code "92") (name "unconnected-(RN3F-2-Pad11)") (class "Default")
      (node (ref "RN3") (pin "11") (pinfunction "2_11") (pintype "passive"))
    )
    (net (code "93") (name "unconnected-(RN4F-1-Pad6)") (class "Default")
      (node (ref "RN4") (pin "6") (pinfunction "1_6") (pintype "passive"))
    )
    (net (code "94") (name "unconnected-(RN4F-2-Pad11)") (class "Default")
      (node (ref "RN4") (pin "11") (pinfunction "2_11") (pintype "passive"))
    )
    (net (code "95") (name "unconnected-(RN4G-1-Pad7)") (class "Default")
      (node (ref "RN4") (pin "7") (pinfunction "1_7") (pintype "passive"))
    )
    (net (code "96") (name "unconnected-(RN4G-2-Pad10)") (class "Default")
      (node (ref "RN4") (pin "10") (pinfunction "2_10") (pintype "passive"))
    )
    (net (code "97") (name "unconnected-(RN4H-1-Pad8)") (class "Default")
      (node (ref "RN4") (pin "8") (pinfunction "1_8") (pintype "passive"))
    )
    (net (code "98") (name "unconnected-(RN4H-2-Pad9)") (class "Default")
      (node (ref "RN4") (pin "9") (pinfunction "2_9") (pintype "passive"))
    )
    (net (code "99") (name "unconnected-(RN5C-1-Pad3)") (class "Default")
      (node (ref "RN5") (pin "3") (pinfunction "1_3") (pintype "passive"))
    )
    (net (code "100") (name "unconnected-(RN5C-2-Pad14)") (class "Default")
      (node (ref "RN5") (pin "14") (pinfunction "2_14") (pintype "passive"))
    )
    (net (code "101") (name "unconnected-(RN5F-1-Pad6)") (class "Default")
      (node (ref "RN5") (pin "6") (pinfunction "1_6") (pintype "passive"))
    )
    (net (code "102") (name "unconnected-(RN5F-2-Pad11)") (class "Default")
      (node (ref "RN5") (pin "11") (pinfunction "2_11") (pintype "passive"))
    )
    (net (code "103") (name "unconnected-(RN6C-1-Pad3)") (class "Default")
      (node (ref "RN6") (pin "3") (pinfunction "1_3") (pintype "passive"))
    )
    (net (code "104") (name "unconnected-(RN6C-2-Pad14)") (class "Default")
      (node (ref "RN6") (pin "14") (pinfunction "2_14") (pintype "passive"))
    )
    (net (code "105") (name "unconnected-(RN6F-1-Pad6)") (class "Default")
      (node (ref "RN6") (pin "6") (pinfunction "1_6") (pintype "passive"))
    )
    (net (code "106") (name "unconnected-(RN6F-2-Pad11)") (class "Default")
      (node (ref "RN6") (pin "11") (pinfunction "2_11") (pintype "passive"))
    )
    (net (code "107") (name "unconnected-(RN6G-1-Pad7)") (class "Default")
      (node (ref "RN6") (pin "7") (pinfunction "1_7") (pintype "passive"))
    )
    (net (code "108") (name "unconnected-(RN6G-2-Pad10)") (class "Default")
      (node (ref "RN6") (pin "10") (pinfunction "2_10") (pintype "passive"))
    )
    (net (code "109") (name "unconnected-(RN6H-1-Pad8)") (class "Default")
      (node (ref "RN6") (pin "8") (pinfunction "1_8") (pintype "passive"))
    )
    (net (code "110") (name "unconnected-(RN6H-2-Pad9)") (class "Default")
      (node (ref "RN6") (pin "9") (pinfunction "2_9") (pintype "passive"))
    )
    (net (code "111") (name "unconnected-(RN8H-1-Pad8)") (class "Default")
      (node (ref "RN8") (pin "8") (pinfunction "1_8") (pintype "passive"))
    )
    (net (code "112") (name "unconnected-(RN8H-2-Pad9)") (class "Default")
      (node (ref "RN8") (pin "9") (pinfunction "2_9") (pintype "passive"))
    )
    (net (code "113") (name "unconnected-(U$1-Pad4)") (class "Default")
      (node (ref "U$1") (pin "4") (pinfunction "4_4") (pintype "passive"))
    )
    (net (code "114") (name "unconnected-(U$1-Pad9)") (class "Default")
      (node (ref "U$1") (pin "9") (pinfunction "9_9") (pintype "passive"))
    )
    (net (code "115") (name "unconnected-(U$1-Pad11)") (class "Default")
      (node (ref "U$1") (pin "11") (pinfunction "11_11") (pintype "passive"))
    )
    (net (code "116") (name "unconnected-(U$1-Pad12)") (class "Default")
      (node (ref "U$1") (pin "12") (pinfunction "12_12") (pintype "passive"))
    )
    (net (code "117") (name "unconnected-(U$1-Pad15)") (class "Default")
      (node (ref "U$1") (pin "15") (pinfunction "15_15") (pintype "passive"))
    )
    (net (code "118") (name "unconnected-(U2-AN2{slash}C2INB{slash}VMIO{slash}RP13{slash}CN4{slash}RB2-Pad14)") (class "Default")
      (node (ref "U2") (pin "14") (pinfunction "AN2/C2INB/VMIO/RP13/CN4/RB2_14") (pintype "bidirectional"))
    )
    (net (code "119") (name "unconnected-(U2-AN3{slash}C2INA{slash}VPIO{slash}CN5{slash}RB3-Pad13)") (class "Default")
      (node (ref "U2") (pin "13") (pinfunction "AN3/C2INA/VPIO/CN5/RB3_13") (pintype "bidirectional"))
    )
    (net (code "120") (name "unconnected-(U2-C3INA{slash}SESSEND{slash}CN16{slash}RD7-Pad55)") (class "Default")
      (node (ref "U2") (pin "55") (pinfunction "C3INA/SESSEND/CN16/RD7_55") (pintype "bidirectional"))
    )
    (net (code "121") (name "unconnected-(U2-C3INB{slash}CN15{slash}RD6-Pad54)") (class "Default")
      (node (ref "U2") (pin "54") (pinfunction "C3INB/CN15/RD6_54") (pintype "bidirectional"))
    )
    (net (code "122") (name "unconnected-(U2-DMH{slash}RP11{slash}INT0{slash}CN49{slash}RD0-Pad46)") (class "Default")
      (node (ref "U2") (pin "46") (pinfunction "DMH/RP11/INT0/CN49/RD0_46") (pintype "bidirectional"))
    )
    (net (code "123") (name "unconnected-(U2-DPH{slash}RP23{slash}CN51{slash}RD2-Pad50)") (class "Default")
      (node (ref "U2") (pin "50") (pinfunction "DPH/RP23/CN51/RD2_50") (pintype "bidirectional"))
    )
    (net (code "124") (name "unconnected-(U2-RTCC{slash}DMLN{slash}RP2{slash}CN53{slash}RD8-Pad42)") (class "Default")
      (node (ref "U2") (pin "42") (pinfunction "RTCC/DMLN/RP2/CN53/RD8_42") (pintype "bidirectional"))
    )
    (net (code "125") (name "unconnected-(U2-SOSCI{slash}C3IND{slash}CN1{slash}RC13-Pad47)") (class "Default")
      (node (ref "U2") (pin "47") (pinfunction "SOSCI/C3IND/CN1/RC13_47") (pintype "bidirectional"))
    )
    (net (code "126") (name "unconnected-(U2-SOSCO{slash}SCLKI{slash}T1CK{slash}C3INC{slash}RPI37{slash}CN0{slash}RC14-Pad48)") (class "Default")
      (node (ref "U2") (pin "48") (pinfunction "SOSCO/SCLKI/T1CK/C3INC/RPI37/CN0/RC14_48") (pintype "bidirectional"))
    )
  )
)
